# adaptador.net
KiCad netlist of a schematic drawn in Altium Designer
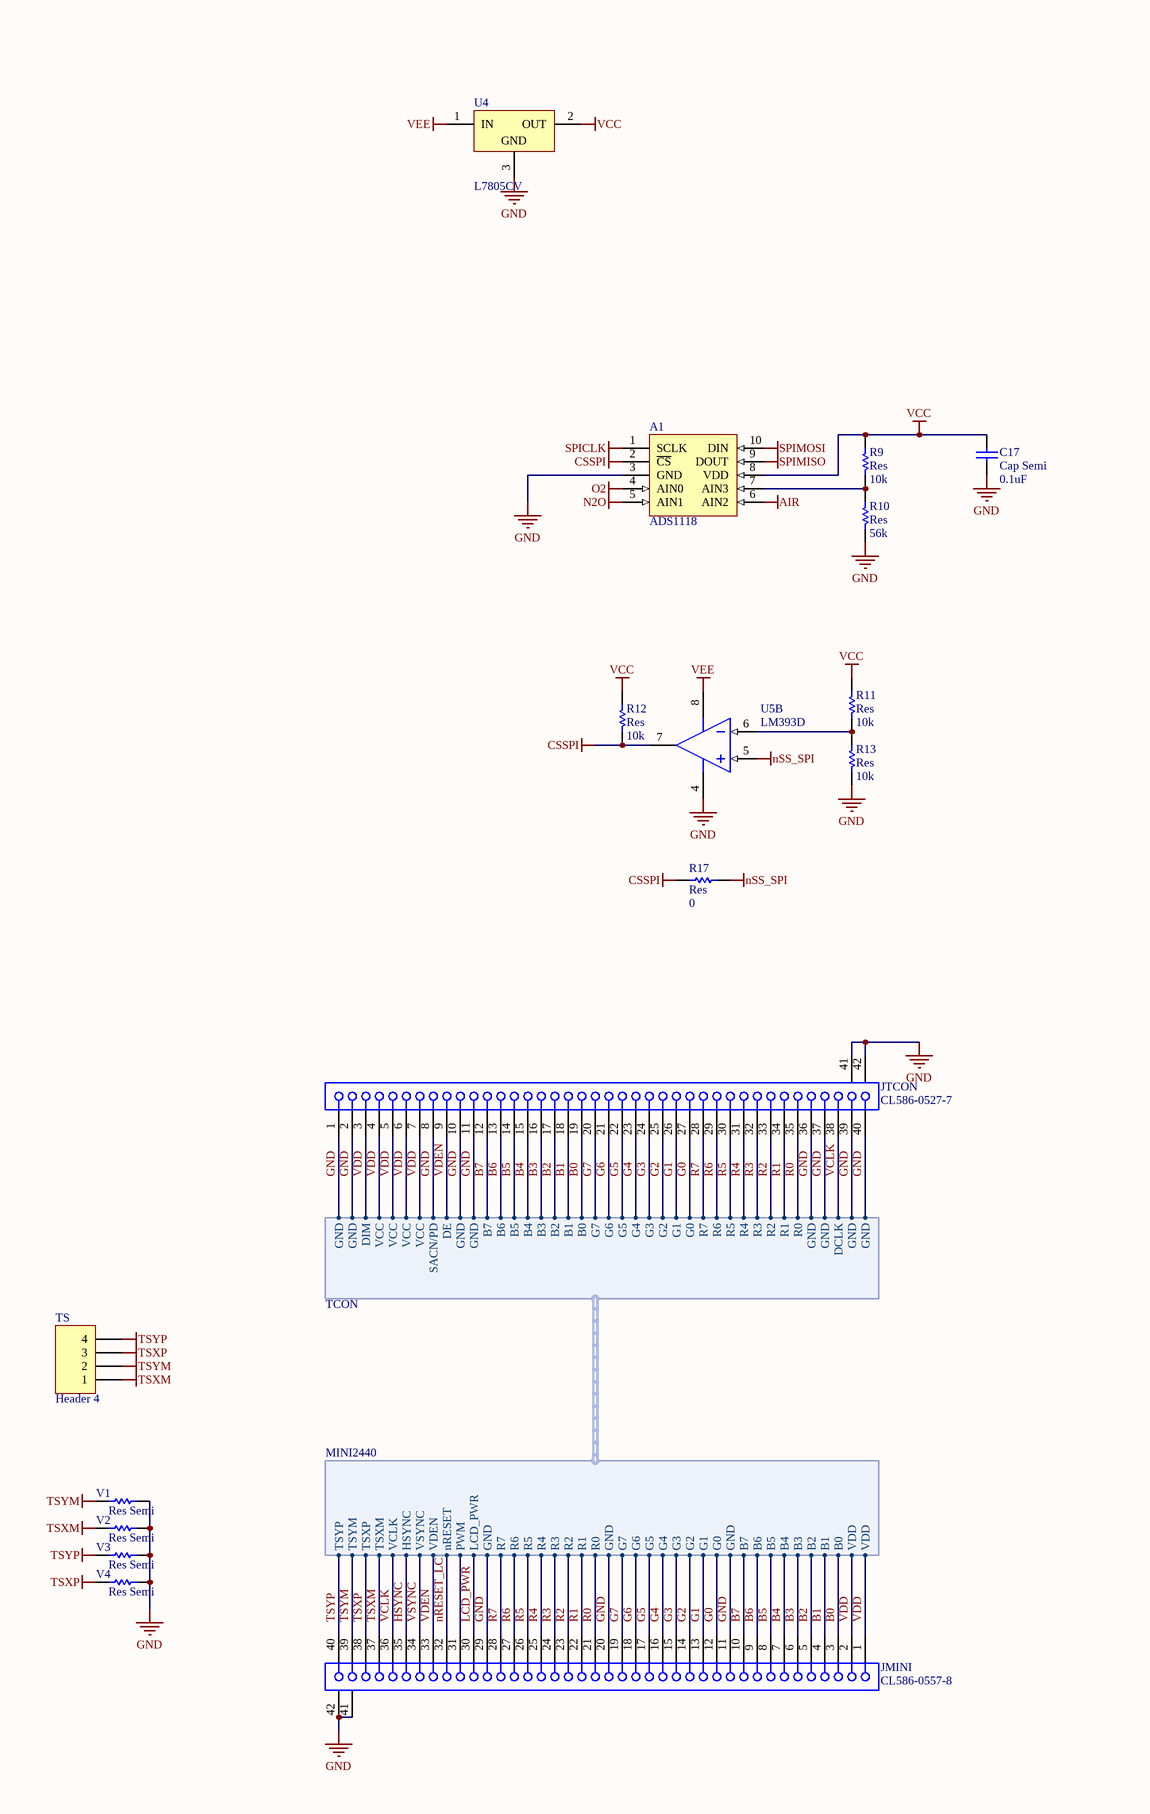
[diagram p0: adaptador.SchDoc, left]
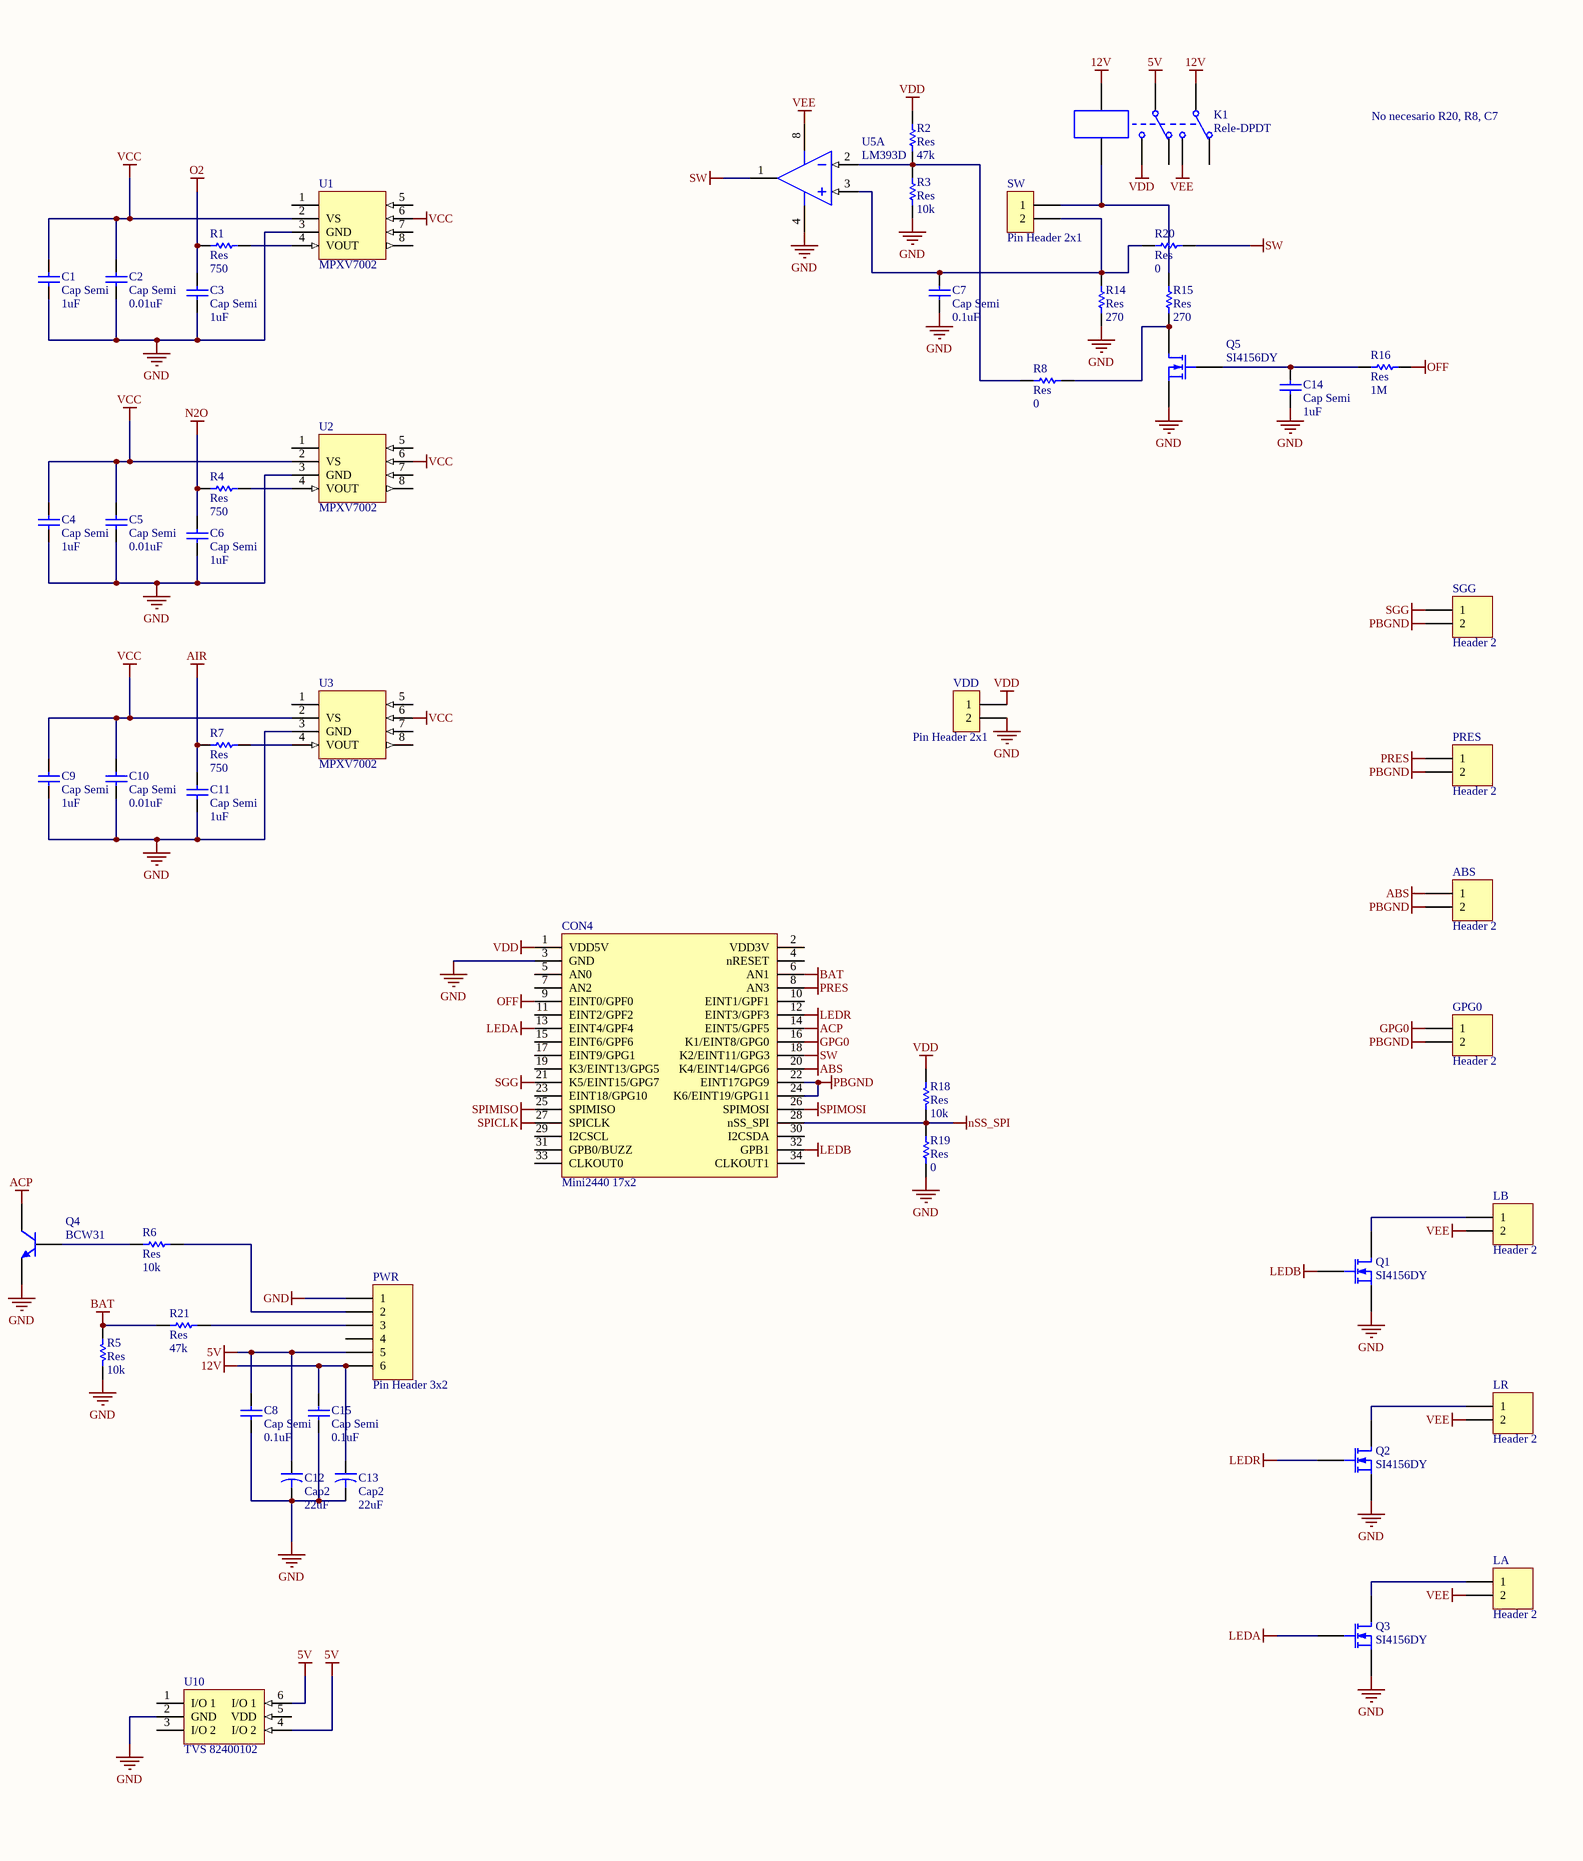
[diagram p1: adaptador.SchDoc, right]

(export (version "E")
  (design (tool "Eeschema 10.0.6"))
  (components
    (comp (ref "A1") (value "ADS1118") (footprint "MSOP-10") (libsource (lib "libreria") (part "ADS1118")))
    (comp (ref "ABS")
      (value "Header 2")
      (footprint "Sherlock2H")
      (description "mini_header 2x1")
      (libsource (lib "Miscellaneous Connectors") (part "Header 2"))
    )
    (comp (ref "C1")
      (value "Cap Semi")
      (footprint "8-1206")
      (description "Capacitor cerámico")
      (fields (field (name "ALTIUM_VALUE") "1uF"))
      (libsource (lib "Miscellaneous Devices") (part "Cap Semi"))
    )
    (comp (ref "C2")
      (value "Cap Semi")
      (footprint "8-1206")
      (description "Capacitor cerámico")
      (fields (field (name "ALTIUM_VALUE") "0.01uF"))
      (libsource (lib "Miscellaneous Devices") (part "Cap Semi"))
    )
    (comp (ref "C3")
      (value "Cap Semi")
      (footprint "8-1206")
      (description "Capacitor cerámico")
      (fields (field (name "ALTIUM_VALUE") "1uF"))
      (libsource (lib "Miscellaneous Devices") (part "Cap Semi"))
    )
    (comp (ref "C4")
      (value "Cap Semi")
      (footprint "8-1206")
      (description "Capacitor cerámico")
      (fields (field (name "ALTIUM_VALUE") "1uF"))
      (libsource (lib "Miscellaneous Devices") (part "Cap Semi"))
    )
    (comp (ref "C5")
      (value "Cap Semi")
      (footprint "8-1206")
      (description "Capacitor cerámico")
      (fields (field (name "ALTIUM_VALUE") "0.01uF"))
      (libsource (lib "Miscellaneous Devices") (part "Cap Semi"))
    )
    (comp (ref "C6")
      (value "Cap Semi")
      (footprint "8-1206")
      (description "Capacitor cerámico")
      (fields (field (name "ALTIUM_VALUE") "1uF"))
      (libsource (lib "Miscellaneous Devices") (part "Cap Semi"))
    )
    (comp (ref "C7")
      (value "Cap Semi")
      (footprint "8-1206")
      (description "Capacitor cerámico")
      (fields (field (name "ALTIUM_VALUE") "0.1uF"))
      (libsource (lib "Miscellaneous Devices") (part "Cap Semi"))
    )
    (comp (ref "C8")
      (value "Cap Semi")
      (footprint "8-1206")
      (description "Capacitor cerámico")
      (fields (field (name "ALTIUM_VALUE") "0.1uF"))
      (libsource (lib "Miscellaneous Devices") (part "Cap Semi"))
    )
    (comp (ref "C9")
      (value "Cap Semi")
      (footprint "8-1206")
      (description "Capacitor cerámico")
      (fields (field (name "ALTIUM_VALUE") "1uF"))
      (libsource (lib "Miscellaneous Devices") (part "Cap Semi"))
    )
    (comp (ref "C10")
      (value "Cap Semi")
      (footprint "8-1206")
      (description "Capacitor cerámico")
      (fields (field (name "ALTIUM_VALUE") "0.01uF"))
      (libsource (lib "Miscellaneous Devices") (part "Cap Semi"))
    )
    (comp (ref "C11")
      (value "Cap Semi")
      (footprint "8-1206")
      (description "Capacitor cerámico")
      (fields (field (name "ALTIUM_VALUE") "1uF"))
      (libsource (lib "Miscellaneous Devices") (part "Cap Semi"))
    )
    (comp (ref "C12")
      (value "Cap2")
      (footprint "CAPPR2-5x6.8")
      (description "Capacitor")
      (fields (field (name "ALTIUM_VALUE") "22uF") (field (name "PUBLISHER") "Altium Limited"))
      (libsource (lib "Miscellaneous Devices") (part "Cap2"))
    )
    (comp (ref "C13")
      (value "Cap2")
      (footprint "CAPPR2-5x6.8")
      (description "Capacitor")
      (fields (field (name "ALTIUM_VALUE") "22uF") (field (name "PUBLISHER") "Altium Limited"))
      (libsource (lib "Miscellaneous Devices") (part "Cap2"))
    )
    (comp (ref "C14")
      (value "Cap Semi")
      (footprint "8-1206")
      (description "Capacitor cerámico")
      (fields (field (name "ALTIUM_VALUE") "1uF"))
      (libsource (lib "Miscellaneous Devices") (part "Cap Semi"))
    )
    (comp (ref "C15")
      (value "Cap Semi")
      (footprint "8-1206")
      (description "Capacitor cerámico")
      (fields (field (name "ALTIUM_VALUE") "0.1uF"))
      (libsource (lib "Miscellaneous Devices") (part "Cap Semi"))
    )
    (comp (ref "C17")
      (value "Cap Semi")
      (footprint "8-1206")
      (description "Capacitor cerámico")
      (fields (field (name "ALTIUM_VALUE") "0.1uF"))
      (libsource (lib "Miscellaneous Devices") (part "Cap Semi"))
    )
    (comp (ref "CON4")
      (value "Mini2440 17x2")
      (footprint "HDR2X17HV")
      (description "Header, 17-Pin, Dual row")
      (fields (field (name "PUBLISHER") "Altium Limited"))
      (libsource (lib "libreria") (part "Mini2440 17x2"))
    )
    (comp (ref "GPG0")
      (value "Header 2")
      (footprint "Sherlock2H")
      (description "mini_header 2x1")
      (libsource (lib "Miscellaneous Connectors") (part "Header 2"))
    )
    (comp (ref "JMINI")
      (value "CL586-0557-8")
      (footprint "FH12-40S-0.5SHD")
      (description "FPC 40pos 0.5mm")
      (fields (field (name "MANUFACTURER") "OMRON") (field (name "PARTNUMBER") "XF2M-4015-1A"))
      (libsource (lib "HRS FPC-FFC FH12 Series") (part "CL586-0557-8"))
    )
    (comp (ref "JTCON")
      (value "CL586-0527-7")
      (footprint "FH12-40S-0.5SHD")
      (description "FPC 40pos 0.5mm")
      (fields (field (name "MANUFACTURER") "OMRON") (field (name "PARTNUMBER") "XF2M-4015-1A"))
      (libsource (lib "HRS FPC-FFC FH12 Series") (part "CL586-0527-7"))
    )
    (comp (ref "K1")
      (value "Rele-DPDT")
      (footprint "RELE-DPDT")
      (description "Dual-Pole Dual-Throw Relay")
      (fields (field (name "PUBLISHER") "Altium Limited"))
      (libsource (lib "libreria") (part "Rele-DPDT"))
    )
    (comp (ref "LA")
      (value "Header 2")
      (footprint "Sherlock2H")
      (description "mini_header 2x1")
      (fields (field (name "MANUFACTURER") "JST") (field (name "PARTNUMBER") "S2B-PH-K-S"))
      (libsource (lib "Miscellaneous Connectors") (part "Header 2"))
    )
    (comp (ref "LB")
      (value "Header 2")
      (footprint "Sherlock2H")
      (description "mini_header 2x1")
      (fields (field (name "MANUFACTURER") "JST") (field (name "PARTNUMBER") "S2B-PH-K-S"))
      (libsource (lib "Miscellaneous Connectors") (part "Header 2"))
    )
    (comp (ref "LR")
      (value "Header 2")
      (footprint "Sherlock2H")
      (description "mini_header 2x1")
      (fields (field (name "MANUFACTURER") "JST") (field (name "PARTNUMBER") "S2B-PH-K-S"))
      (libsource (lib "Miscellaneous Connectors") (part "Header 2"))
    )
    (comp (ref "PRES")
      (value "Header 2")
      (footprint "Sherlock2H")
      (description "mini_header 2x1")
      (fields (field (name "MANUFACTURER") "JST") (field (name "PARTNUMBER") "S2B-PH-K-S"))
      (libsource (lib "Miscellaneous Connectors") (part "Header 2"))
    )
    (comp (ref "PWR")
      (value "Pin Header 3x2")
      (footprint "bigHDR2X3")
      (description "Minifit 6pos v/h 4.2mm")
      (fields (field (name "MANUFACTURER") "JST") (field (name "PARTNUMBER") "S2B-PH-K-S"))
      (libsource (lib "libreria") (part "Vertical Pin Header 3x2"))
    )
    (comp (ref "Q1")
      (value "SI4156DY")
      (footprint "SO8_M_MOSFET")
      (description "N-Channel MOSFET")
      (fields (field (name "MANUFACTURER") "Vishay"))
      (libsource (lib "Miscellaneous Devices") (part "MOSFET-N"))
    )
    (comp (ref "Q2")
      (value "SI4156DY")
      (footprint "SO8_M_MOSFET")
      (description "N-Channel MOSFET")
      (fields (field (name "MANUFACTURER") "Vishay"))
      (libsource (lib "Miscellaneous Devices") (part "MOSFET-N"))
    )
    (comp (ref "Q3")
      (value "SI4156DY")
      (footprint "SO8_M_MOSFET")
      (description "N-Channel MOSFET")
      (fields (field (name "MANUFACTURER") "Vishay"))
      (libsource (lib "Miscellaneous Devices") (part "MOSFET-N"))
    )
    (comp (ref "Q4")
      (value "BCW31")
      (footprint "SOT-23A")
      (description "NPN Epitaxial Silicon Transistor")
      (fields (field (name "PUBLISHER") "Altium Limited"))
      (libsource (lib "FSC Discrete BJT") (part "BCW31"))
    )
    (comp (ref "Q5")
      (value "SI4156DY")
      (footprint "SO8_M_MOSFET")
      (description "N-Channel MOSFET")
      (fields (field (name "MANUFACTURER") "Vishay"))
      (libsource (lib "Miscellaneous Devices") (part "MOSFET-N"))
    )
    (comp (ref "R1")
      (value "Res")
      (footprint "8-1206")
      (description "Resistor")
      (fields (field (name "ALTIUM_VALUE") "750"))
      (libsource (lib "libreria") (part "Res"))
    )
    (comp (ref "R2")
      (value "Res")
      (footprint "8-1206")
      (description "Resistor")
      (fields (field (name "ALTIUM_VALUE") "47k"))
      (libsource (lib "libreria") (part "Res"))
    )
    (comp (ref "R3")
      (value "Res")
      (footprint "8-1206")
      (description "Resistor")
      (fields (field (name "ALTIUM_VALUE") "10k"))
      (libsource (lib "libreria") (part "Res"))
    )
    (comp (ref "R4")
      (value "Res")
      (footprint "8-1206")
      (description "Resistor")
      (fields (field (name "ALTIUM_VALUE") "750"))
      (libsource (lib "libreria") (part "Res"))
    )
    (comp (ref "R5")
      (value "Res")
      (footprint "8-1206")
      (description "Resistor")
      (fields (field (name "ALTIUM_VALUE") "10k"))
      (libsource (lib "libreria") (part "Res"))
    )
    (comp (ref "R6")
      (value "Res")
      (footprint "8-1206")
      (description "Resistor")
      (fields (field (name "ALTIUM_VALUE") "10k"))
      (libsource (lib "libreria") (part "Res"))
    )
    (comp (ref "R7")
      (value "Res")
      (footprint "8-1206")
      (description "Resistor")
      (fields (field (name "ALTIUM_VALUE") "750"))
      (libsource (lib "libreria") (part "Res"))
    )
    (comp (ref "R8")
      (value "Res")
      (footprint "8-1206")
      (description "Resistor")
      (fields (field (name "ALTIUM_VALUE") "0"))
      (libsource (lib "libreria") (part "Res"))
    )
    (comp (ref "R9")
      (value "Res")
      (footprint "8-1206")
      (description "Resistor")
      (fields (field (name "ALTIUM_VALUE") "10k"))
      (libsource (lib "libreria") (part "Res"))
    )
    (comp (ref "R10")
      (value "Res")
      (footprint "8-1206")
      (description "Resistor")
      (fields (field (name "ALTIUM_VALUE") "56k"))
      (libsource (lib "libreria") (part "Res"))
    )
    (comp (ref "R11")
      (value "Res")
      (footprint "8-1206")
      (description "Resistor")
      (fields (field (name "ALTIUM_VALUE") "10k"))
      (libsource (lib "libreria") (part "Res"))
    )
    (comp (ref "R12")
      (value "Res")
      (footprint "8-1206")
      (description "Resistor")
      (fields (field (name "ALTIUM_VALUE") "10k"))
      (libsource (lib "libreria") (part "Res"))
    )
    (comp (ref "R13")
      (value "Res")
      (footprint "8-1206")
      (description "Resistor")
      (fields (field (name "ALTIUM_VALUE") "10k"))
      (libsource (lib "libreria") (part "Res"))
    )
    (comp (ref "R14")
      (value "Res")
      (footprint "8-1206")
      (description "Resistor")
      (fields (field (name "ALTIUM_VALUE") "270"))
      (libsource (lib "libreria") (part "Res"))
    )
    (comp (ref "R15")
      (value "Res")
      (footprint "8-1206")
      (description "Resistor")
      (fields (field (name "ALTIUM_VALUE") "270"))
      (libsource (lib "libreria") (part "Res"))
    )
    (comp (ref "R16")
      (value "Res")
      (footprint "8-1206")
      (description "Resistor")
      (fields (field (name "ALTIUM_VALUE") "1M"))
      (libsource (lib "libreria") (part "Res"))
    )
    (comp (ref "R17")
      (value "Res")
      (footprint "8-1206")
      (description "Resistor")
      (fields (field (name "ALTIUM_VALUE") "0"))
      (libsource (lib "libreria") (part "Res"))
    )
    (comp (ref "R18")
      (value "Res")
      (footprint "8-1206")
      (description "Resistor")
      (fields (field (name "ALTIUM_VALUE") "10k"))
      (libsource (lib "libreria") (part "Res"))
    )
    (comp (ref "R19")
      (value "Res")
      (footprint "8-1206")
      (description "Resistor")
      (fields (field (name "ALTIUM_VALUE") "0"))
      (libsource (lib "libreria") (part "Res"))
    )
    (comp (ref "R20")
      (value "Res")
      (footprint "8-1206")
      (description "Resistor")
      (fields (field (name "ALTIUM_VALUE") "0"))
      (libsource (lib "libreria") (part "Res"))
    )
    (comp (ref "R21")
      (value "Res")
      (footprint "8-1206")
      (description "Resistor")
      (fields (field (name "ALTIUM_VALUE") "47k"))
      (libsource (lib "libreria") (part "Res"))
    )
    (comp (ref "SGG")
      (value "Header 2")
      (footprint "Sherlock2H")
      (description "mini_header 2x1")
      (fields (field (name "MANUFACTURER") "JST") (field (name "PARTNUMBER") "S2B-PH-K-S"))
      (libsource (lib "Miscellaneous Connectors") (part "Header 2"))
    )
    (comp (ref "SW")
      (value "Pin Header 2x1")
      (footprint "Sherlock2H")
      (description "mini_header 2x1")
      (fields (field (name "MANUFACTURER") "JST") (field (name "PARTNUMBER") "S2B-PH-K-S"))
      (libsource (lib "libreria") (part "Vertical Pin Header PCB 2x1"))
    )
    (comp (ref "TS")
      (value "Header 4")
      (footprint "HDR1X4")
      (description "Header 4pos 2.54mm")
      (libsource (lib "Miscellaneous Connectors") (part "Header 4"))
    )
    (comp (ref "U1")
      (value "MPXV7002")
      (footprint "CASE 1351-01")
      (description "Sensor de presión diferencial")
      (libsource (lib "libreria") (part "MPXV7002"))
    )
    (comp (ref "U2")
      (value "MPXV7002")
      (footprint "CASE 1351-01")
      (description "Sensor de presión diferencial")
      (libsource (lib "libreria") (part "MPXV7002"))
    )
    (comp (ref "U3")
      (value "MPXV7002")
      (footprint "CASE 1351-01")
      (description "Sensor de presión diferencial")
      (libsource (lib "libreria") (part "MPXV7002"))
    )
    (comp (ref "U4")
      (value "L7805CV")
      (footprint "TO220ABN")
      (description "Positive Voltage Regulator")
      (fields (field (name "PUBLISHER") "Altium Limited"))
      (libsource (lib "ST Power Mgt Voltage Regulator") (part "L7805CV"))
    )
    (comp (ref "U5")
      (value "LM393D")
      (footprint "SO8_M")
      (description "Low-Power Dual Voltage Comparator")
      (fields (field (name "PUBLISHER") "Altium Limited"))
      (libsource (lib "ST Analog Comparator") (part "LM393D"))
    )
    (comp (ref "U10")
      (value "TVS 82400102")
      (footprint "SOT23-6")
      (description "Electric Field Imaging Device")
      (libsource (lib "libreria") (part "TVS 82400102"))
    )
    (comp (ref "V1")
      (value "Res Semi")
      (footprint "RESC1608L")
      (description "Semiconductor Resistor")
      (fields (field (name "PUBLISHER") "Altium Limited"))
      (libsource (lib "Miscellaneous Devices") (part "Res Semi"))
    )
    (comp (ref "V2")
      (value "Res Semi")
      (footprint "RESC1608L")
      (description "Semiconductor Resistor")
      (fields (field (name "PUBLISHER") "Altium Limited"))
      (libsource (lib "Miscellaneous Devices") (part "Res Semi"))
    )
    (comp (ref "V3")
      (value "Res Semi")
      (footprint "RESC1608L")
      (description "Semiconductor Resistor")
      (fields (field (name "PUBLISHER") "Altium Limited"))
      (libsource (lib "Miscellaneous Devices") (part "Res Semi"))
    )
    (comp (ref "V4")
      (value "Res Semi")
      (footprint "RESC1608L")
      (description "Semiconductor Resistor")
      (fields (field (name "PUBLISHER") "Altium Limited"))
      (libsource (lib "Miscellaneous Devices") (part "Res Semi"))
    )
    (comp (ref "VDD")
      (value "Pin Header 2x1")
      (footprint "Sherlock2H")
      (description "mini_header 2x1")
      (fields (field (name "MANUFACTURER") "JST") (field (name "PARTNUMBER") "S2B-PH-K-S"))
      (libsource (lib "libreria") (part "Vertical Pin Header PCB 2x1"))
    )
  )
  (nets
    (net (code "2") (name "/B0") (class "Default")
      (node (ref "JMINI") (pin "3") (pinfunction "3_3") (pintype "passive"))
      (node (ref "JTCON") (pin "19") (pinfunction "19_19") (pintype "passive"))
    )
    (net (code "3") (name "/B1") (class "Default")
      (node (ref "JMINI") (pin "4") (pinfunction "4_4") (pintype "passive"))
      (node (ref "JTCON") (pin "18") (pinfunction "18_18") (pintype "passive"))
    )
    (net (code "4") (name "/B2") (class "Default")
      (node (ref "JMINI") (pin "5") (pinfunction "5_5") (pintype "passive"))
      (node (ref "JTCON") (pin "17") (pinfunction "17_17") (pintype "passive"))
    )
    (net (code "5") (name "/B3") (class "Default")
      (node (ref "JMINI") (pin "6") (pinfunction "6_6") (pintype "passive"))
      (node (ref "JTCON") (pin "16") (pinfunction "16_16") (pintype "passive"))
    )
    (net (code "6") (name "/B4") (class "Default")
      (node (ref "JMINI") (pin "7") (pinfunction "7_7") (pintype "passive"))
      (node (ref "JTCON") (pin "15") (pinfunction "15_15") (pintype "passive"))
    )
    (net (code "7") (name "/B5") (class "Default")
      (node (ref "JMINI") (pin "8") (pinfunction "8_8") (pintype "passive"))
      (node (ref "JTCON") (pin "14") (pinfunction "14_14") (pintype "passive"))
    )
    (net (code "8") (name "/B6") (class "Default")
      (node (ref "JMINI") (pin "9") (pinfunction "9_9") (pintype "passive"))
      (node (ref "JTCON") (pin "13") (pinfunction "13_13") (pintype "passive"))
    )
    (net (code "9") (name "/B7") (class "Default")
      (node (ref "JMINI") (pin "10") (pinfunction "10_10") (pintype "passive"))
      (node (ref "JTCON") (pin "12") (pinfunction "12_12") (pintype "passive"))
    )
    (net (code "10") (name "/G0") (class "Default")
      (node (ref "JMINI") (pin "12") (pinfunction "12_12") (pintype "passive"))
      (node (ref "JTCON") (pin "27") (pinfunction "27_27") (pintype "passive"))
    )
    (net (code "11") (name "/G1") (class "Default")
      (node (ref "JMINI") (pin "13") (pinfunction "13_13") (pintype "passive"))
      (node (ref "JTCON") (pin "26") (pinfunction "26_26") (pintype "passive"))
    )
    (net (code "12") (name "/G2") (class "Default")
      (node (ref "JMINI") (pin "14") (pinfunction "14_14") (pintype "passive"))
      (node (ref "JTCON") (pin "25") (pinfunction "25_25") (pintype "passive"))
    )
    (net (code "13") (name "/G3") (class "Default")
      (node (ref "JMINI") (pin "15") (pinfunction "15_15") (pintype "passive"))
      (node (ref "JTCON") (pin "24") (pinfunction "24_24") (pintype "passive"))
    )
    (net (code "14") (name "/G4") (class "Default")
      (node (ref "JMINI") (pin "16") (pinfunction "16_16") (pintype "passive"))
      (node (ref "JTCON") (pin "23") (pinfunction "23_23") (pintype "passive"))
    )
    (net (code "15") (name "/G5") (class "Default")
      (node (ref "JMINI") (pin "17") (pinfunction "17_17") (pintype "passive"))
      (node (ref "JTCON") (pin "22") (pinfunction "22_22") (pintype "passive"))
    )
    (net (code "16") (name "/G6") (class "Default")
      (node (ref "JMINI") (pin "18") (pinfunction "18_18") (pintype "passive"))
      (node (ref "JTCON") (pin "21") (pinfunction "21_21") (pintype "passive"))
    )
    (net (code "17") (name "/G7") (class "Default")
      (node (ref "JMINI") (pin "19") (pinfunction "19_19") (pintype "passive"))
      (node (ref "JTCON") (pin "20") (pinfunction "20_20") (pintype "passive"))
    )
    (net (code "18") (name "/HSYNC") (class "Default")
      (node (ref "JMINI") (pin "35") (pinfunction "35_35") (pintype "passive"))
    )
    (net (code "19") (name "/LCD_PWR") (class "Default")
      (node (ref "JMINI") (pin "30") (pinfunction "30_30") (pintype "passive"))
    )
    (net (code "20") (name "/PWM") (class "Default")
      (node (ref "JMINI") (pin "31") (pinfunction "31_31") (pintype "passive"))
    )
    (net (code "21") (name "/R0") (class "Default")
      (node (ref "JMINI") (pin "21") (pinfunction "21_21") (pintype "passive"))
      (node (ref "JTCON") (pin "35") (pinfunction "35_35") (pintype "passive"))
    )
    (net (code "22") (name "/R1") (class "Default")
      (node (ref "JMINI") (pin "22") (pinfunction "22_22") (pintype "passive"))
      (node (ref "JTCON") (pin "34") (pinfunction "34_34") (pintype "passive"))
    )
    (net (code "23") (name "/R2") (class "Default")
      (node (ref "JMINI") (pin "23") (pinfunction "23_23") (pintype "passive"))
      (node (ref "JTCON") (pin "33") (pinfunction "33_33") (pintype "passive"))
    )
    (net (code "24") (name "/R3") (class "Default")
      (node (ref "JMINI") (pin "24") (pinfunction "24_24") (pintype "passive"))
      (node (ref "JTCON") (pin "32") (pinfunction "32_32") (pintype "passive"))
    )
    (net (code "25") (name "/R4") (class "Default")
      (node (ref "JMINI") (pin "25") (pinfunction "25_25") (pintype "passive"))
      (node (ref "JTCON") (pin "31") (pinfunction "31_31") (pintype "passive"))
    )
    (net (code "26") (name "/R5") (class "Default")
      (node (ref "JMINI") (pin "26") (pinfunction "26_26") (pintype "passive"))
      (node (ref "JTCON") (pin "30") (pinfunction "30_30") (pintype "passive"))
    )
    (net (code "27") (name "/R6") (class "Default")
      (node (ref "JMINI") (pin "27") (pinfunction "27_27") (pintype "passive"))
      (node (ref "JTCON") (pin "29") (pinfunction "29_29") (pintype "passive"))
    )
    (net (code "28") (name "/R7") (class "Default")
      (node (ref "JMINI") (pin "28") (pinfunction "28_28") (pintype "passive"))
      (node (ref "JTCON") (pin "28") (pinfunction "28_28") (pintype "passive"))
    )
    (net (code "29") (name "/VCLK") (class "Default")
      (node (ref "JMINI") (pin "36") (pinfunction "36_36") (pintype "passive"))
      (node (ref "JTCON") (pin "38") (pinfunction "38_38") (pintype "passive"))
    )
    (net (code "30") (name "/VDEN") (class "Default")
      (node (ref "JMINI") (pin "33") (pinfunction "33_33") (pintype "passive"))
      (node (ref "JTCON") (pin "9") (pinfunction "9_9") (pintype "passive"))
    )
    (net (code "31") (name "/VSYNC") (class "Default")
      (node (ref "JMINI") (pin "34") (pinfunction "34_34") (pintype "passive"))
    )
    (net (code "32") (name "/nRESET_LCD") (class "Default")
      (node (ref "JMINI") (pin "32") (pinfunction "32_32") (pintype "passive"))
    )
    (net (code "34") (name "5V") (class "Default")
      (node (ref "C12") (pin "1") (pinfunction "1_1") (pintype "passive"))
      (node (ref "C8") (pin "2") (pinfunction "2_2") (pintype "passive"))
      (node (ref "K1") (pin "7") (pinfunction "7_7") (pintype "passive"))
      (node (ref "PWR") (pin "5") (pinfunction "5_5") (pintype "passive"))
      (node (ref "U10") (pin "4") (pinfunction "I/O_2_4") (pintype "input"))
      (node (ref "U10") (pin "6") (pinfunction "I/O_1_6") (pintype "input"))
    )
    (net (code "35") (name "12V") (class "Default")
      (node (ref "C13") (pin "1") (pinfunction "1_1") (pintype "passive"))
      (node (ref "C15") (pin "2") (pinfunction "2_2") (pintype "passive"))
      (node (ref "K1") (pin "2") (pinfunction "2_2") (pintype "passive"))
      (node (ref "K1") (pin "8") (pinfunction "8_8") (pintype "passive"))
      (node (ref "PWR") (pin "6") (pinfunction "6_6") (pintype "passive"))
    )
    (net (code "36") (name "ABS") (class "Default")
      (node (ref "ABS") (pin "1") (pinfunction "1_1") (pintype "passive"))
      (node (ref "CON4") (pin "20") (pinfunction "K4/EINT14/GPG6_20") (pintype "passive"))
    )
    (net (code "37") (name "ACP") (class "Default")
      (node (ref "CON4") (pin "14") (pinfunction "EINT5/GPF5_14") (pintype "passive"))
      (node (ref "Q4") (pin "3") (pinfunction "C_3") (pintype "passive"))
    )
    (net (code "38") (name "AIR") (class "Default")
      (node (ref "A1") (pin "6") (pinfunction "AIN2_6") (pintype "input"))
      (node (ref "C11") (pin "2") (pinfunction "2_2") (pintype "passive"))
      (node (ref "R7") (pin "1") (pinfunction "1_1") (pintype "passive"))
    )
    (net (code "39") (name "BAT") (class "Default")
      (node (ref "CON4") (pin "6") (pinfunction "AN1_6") (pintype "passive"))
      (node (ref "R21") (pin "2") (pinfunction "2_2") (pintype "passive"))
      (node (ref "R5") (pin "1") (pinfunction "1_1") (pintype "passive"))
    )
    (net (code "40") (name "CSSPI") (class "Default")
      (node (ref "A1") (pin "2") (pinfunction "~{CS}_2") (pintype "power_in"))
      (node (ref "R12") (pin "2") (pinfunction "2_2") (pintype "passive"))
      (node (ref "R17") (pin "2") (pinfunction "2_2") (pintype "passive"))
      (node (ref "U5") (pin "7") (pinfunction "OUT_7") (pintype "open_collector"))
    )
    (net (code "41") (name "GND") (class "Default")
      (node (ref "A1") (pin "3") (pinfunction "GND_3") (pintype "power_in"))
      (node (ref "C1") (pin "1") (pinfunction "1_1") (pintype "passive"))
      (node (ref "C10") (pin "1") (pinfunction "1_1") (pintype "passive"))
      (node (ref "C11") (pin "1") (pinfunction "1_1") (pintype "passive"))
      (node (ref "C12") (pin "2") (pinfunction "2_2") (pintype "passive"))
      (node (ref "C13") (pin "2") (pinfunction "2_2") (pintype "passive"))
      (node (ref "C14") (pin "1") (pinfunction "1_1") (pintype "passive"))
      (node (ref "C15") (pin "1") (pinfunction "1_1") (pintype "passive"))
      (node (ref "C17") (pin "1") (pinfunction "1_1") (pintype "passive"))
      (node (ref "C2") (pin "1") (pinfunction "1_1") (pintype "passive"))
      (node (ref "C3") (pin "1") (pinfunction "1_1") (pintype "passive"))
      (node (ref "C4") (pin "1") (pinfunction "1_1") (pintype "passive"))
      (node (ref "C5") (pin "1") (pinfunction "1_1") (pintype "passive"))
      (node (ref "C6") (pin "1") (pinfunction "1_1") (pintype "passive"))
      (node (ref "C7") (pin "1") (pinfunction "1_1") (pintype "passive"))
      (node (ref "C8") (pin "1") (pinfunction "1_1") (pintype "passive"))
      (node (ref "C9") (pin "1") (pinfunction "1_1") (pintype "passive"))
      (node (ref "CON4") (pin "3") (pinfunction "GND_3") (pintype "passive"))
      (node (ref "JMINI") (pin "11") (pinfunction "11_11") (pintype "passive"))
      (node (ref "JMINI") (pin "20") (pinfunction "20_20") (pintype "passive"))
      (node (ref "JMINI") (pin "29") (pinfunction "29_29") (pintype "passive"))
      (node (ref "JMINI") (pin "41") (pinfunction "MH1_41") (pintype "passive"))
      (node (ref "JMINI") (pin "42") (pinfunction "MH2_42") (pintype "passive"))
      (node (ref "JTCON") (pin "1") (pinfunction "1_1") (pintype "passive"))
      (node (ref "JTCON") (pin "10") (pinfunction "10_10") (pintype "passive"))
      (node (ref "JTCON") (pin "11") (pinfunction "11_11") (pintype "passive"))
      (node (ref "JTCON") (pin "2") (pinfunction "2_2") (pintype "passive"))
      (node (ref "JTCON") (pin "36") (pinfunction "36_36") (pintype "passive"))
      (node (ref "JTCON") (pin "37") (pinfunction "37_37") (pintype "passive"))
      (node (ref "JTCON") (pin "39") (pinfunction "39_39") (pintype "passive"))
      (node (ref "JTCON") (pin "40") (pinfunction "40_40") (pintype "passive"))
      (node (ref "JTCON") (pin "41") (pinfunction "MH1_41") (pintype "passive"))
      (node (ref "JTCON") (pin "42") (pinfunction "MH2_42") (pintype "passive"))
      (node (ref "JTCON") (pin "8") (pinfunction "8_8") (pintype "passive"))
      (node (ref "PWR") (pin "1") (pinfunction "1_1") (pintype "passive"))
      (node (ref "Q1") (pin "3") (pinfunction "S_3") (pintype "passive"))
      (node (ref "Q2") (pin "3") (pinfunction "S_3") (pintype "passive"))
      (node (ref "Q3") (pin "3") (pinfunction "S_3") (pintype "passive"))
      (node (ref "Q4") (pin "2") (pinfunction "E_2") (pintype "passive"))
      (node (ref "Q5") (pin "3") (pinfunction "S_3") (pintype "passive"))
      (node (ref "R10") (pin "1") (pinfunction "1_1") (pintype "passive"))
      (node (ref "R13") (pin "2") (pinfunction "2_2") (pintype "passive"))
      (node (ref "R14") (pin "1") (pinfunction "1_1") (pintype "passive"))
      (node (ref "R19") (pin "2") (pinfunction "2_2") (pintype "passive"))
      (node (ref "R3") (pin "1") (pinfunction "1_1") (pintype "passive"))
      (node (ref "R5") (pin "2") (pinfunction "2_2") (pintype "passive"))
      (node (ref "U1") (pin "3") (pinfunction "GND_3") (pintype "power_in"))
      (node (ref "U10") (pin "2") (pinfunction "GND_2") (pintype "power_in"))
      (node (ref "U2") (pin "3") (pinfunction "GND_3") (pintype "power_in"))
      (node (ref "U3") (pin "3") (pinfunction "GND_3") (pintype "power_in"))
      (node (ref "U4") (pin "3") (pinfunction "GND_3") (pintype "power_in"))
      (node (ref "U5") (pin "4") (pinfunction "V-_4") (pintype "power_in"))
      (node (ref "V1") (pin "2") (pinfunction "2_2") (pintype "passive"))
      (node (ref "V2") (pin "2") (pinfunction "2_2") (pintype "passive"))
      (node (ref "V3") (pin "2") (pinfunction "2_2") (pintype "passive"))
      (node (ref "V4") (pin "2") (pinfunction "2_2") (pintype "passive"))
      (node (ref "VDD") (pin "2") (pinfunction "2_2") (pintype "passive"))
    )
    (net (code "42") (name "GPG0") (class "Default")
      (node (ref "CON4") (pin "16") (pinfunction "K1/EINT8/GPG0_16") (pintype "passive"))
      (node (ref "GPG0") (pin "1") (pinfunction "1_1") (pintype "passive"))
    )
    (net (code "43") (name "LEDA") (class "Default")
      (node (ref "CON4") (pin "13") (pinfunction "EINT4/GPF4_13") (pintype "passive"))
      (node (ref "Q3") (pin "2") (pinfunction "G_2") (pintype "passive"))
    )
    (net (code "44") (name "LEDB") (class "Default")
      (node (ref "CON4") (pin "32") (pinfunction "GPB1_32") (pintype "passive"))
      (node (ref "Q1") (pin "2") (pinfunction "G_2") (pintype "passive"))
    )
    (net (code "45") (name "LEDR") (class "Default")
      (node (ref "CON4") (pin "12") (pinfunction "EINT3/GPF3_12") (pintype "passive"))
      (node (ref "Q2") (pin "2") (pinfunction "G_2") (pintype "passive"))
    )
    (net (code "46") (name "N2O") (class "Default")
      (node (ref "A1") (pin "5") (pinfunction "AIN1_5") (pintype "input"))
      (node (ref "C6") (pin "2") (pinfunction "2_2") (pintype "passive"))
      (node (ref "R4") (pin "1") (pinfunction "1_1") (pintype "passive"))
    )
    (net (code "47") (name "Net-(A1-AIN3)") (class "Default")
      (node (ref "A1") (pin "7") (pinfunction "AIN3_7") (pintype "input"))
      (node (ref "R10") (pin "2") (pinfunction "2_2") (pintype "passive"))
      (node (ref "R9") (pin "1") (pinfunction "1_1") (pintype "passive"))
    )
    (net (code "48") (name "Net-(K1-Pad1)") (class "Default")
      (node (ref "K1") (pin "1") (pinfunction "1_1") (pintype "passive"))
      (node (ref "R15") (pin "2") (pinfunction "2_2") (pintype "passive"))
      (node (ref "SW") (pin "1") (pinfunction "1_1") (pintype "passive"))
    )
    (net (code "49") (name "Net-(PWR-Pad2)") (class "Default")
      (node (ref "PWR") (pin "2") (pinfunction "2_2") (pintype "passive"))
      (node (ref "R6") (pin "2") (pinfunction "2_2") (pintype "passive"))
    )
    (net (code "50") (name "Net-(PWR-Pad3)") (class "Default")
      (node (ref "PWR") (pin "3") (pinfunction "3_3") (pintype "passive"))
      (node (ref "R21") (pin "1") (pinfunction "1_1") (pintype "passive"))
    )
    (net (code "51") (name "Net-(Q1-D)") (class "Default")
      (node (ref "LB") (pin "1") (pinfunction "1_1") (pintype "passive"))
      (node (ref "Q1") (pin "1") (pinfunction "D_1") (pintype "passive"))
    )
    (net (code "52") (name "Net-(Q2-D)") (class "Default")
      (node (ref "LR") (pin "1") (pinfunction "1_1") (pintype "passive"))
      (node (ref "Q2") (pin "1") (pinfunction "D_1") (pintype "passive"))
    )
    (net (code "53") (name "Net-(Q3-D)") (class "Default")
      (node (ref "LA") (pin "1") (pinfunction "1_1") (pintype "passive"))
      (node (ref "Q3") (pin "1") (pinfunction "D_1") (pintype "passive"))
    )
    (net (code "54") (name "Net-(Q4-B)") (class "Default")
      (node (ref "Q4") (pin "1") (pinfunction "B_1") (pintype "passive"))
      (node (ref "R6") (pin "1") (pinfunction "1_1") (pintype "passive"))
    )
    (net (code "55") (name "Net-(Q5-D)") (class "Default")
      (node (ref "Q5") (pin "1") (pinfunction "D_1") (pintype "passive"))
      (node (ref "R15") (pin "1") (pinfunction "1_1") (pintype "passive"))
      (node (ref "R8") (pin "1") (pinfunction "1_1") (pintype "passive"))
    )
    (net (code "56") (name "Net-(Q5-G)") (class "Default")
      (node (ref "C14") (pin "2") (pinfunction "2_2") (pintype "passive"))
      (node (ref "Q5") (pin "2") (pinfunction "G_2") (pintype "passive"))
      (node (ref "R16") (pin "2") (pinfunction "2_2") (pintype "passive"))
    )
    (net (code "57") (name "Net-(U1-VOUT)") (class "Default")
      (node (ref "R1") (pin "2") (pinfunction "2_2") (pintype "passive"))
      (node (ref "U1") (pin "4") (pinfunction "VOUT_4") (pintype "input"))
    )
    (net (code "58") (name "Net-(U2-VOUT)") (class "Default")
      (node (ref "R4") (pin "2") (pinfunction "2_2") (pintype "passive"))
      (node (ref "U2") (pin "4") (pinfunction "VOUT_4") (pintype "input"))
    )
    (net (code "59") (name "Net-(U3-VOUT)") (class "Default")
      (node (ref "R7") (pin "2") (pinfunction "2_2") (pintype "passive"))
      (node (ref "U3") (pin "4") (pinfunction "VOUT_4") (pintype "input"))
    )
    (net (code "60") (name "Net-(U5A-IN+)") (class "Default")
      (node (ref "C7") (pin "2") (pinfunction "2_2") (pintype "passive"))
      (node (ref "R14") (pin "2") (pinfunction "2_2") (pintype "passive"))
      (node (ref "R20") (pin "2") (pinfunction "2_2") (pintype "passive"))
      (node (ref "SW") (pin "2") (pinfunction "2_2") (pintype "passive"))
      (node (ref "U5") (pin "3") (pinfunction "IN+_3") (pintype "input"))
    )
    (net (code "61") (name "Net-(U5A-IN-)") (class "Default")
      (node (ref "R2") (pin "1") (pinfunction "1_1") (pintype "passive"))
      (node (ref "R3") (pin "2") (pinfunction "2_2") (pintype "passive"))
      (node (ref "R8") (pin "2") (pinfunction "2_2") (pintype "passive"))
      (node (ref "U5") (pin "2") (pinfunction "IN-_2") (pintype "input"))
    )
    (net (code "62") (name "Net-(U5B-IN-)") (class "Default")
      (node (ref "R11") (pin "2") (pinfunction "2_2") (pintype "passive"))
      (node (ref "R13") (pin "1") (pinfunction "1_1") (pintype "passive"))
      (node (ref "U5") (pin "6") (pinfunction "IN-_6") (pintype "input"))
    )
    (net (code "63") (name "O2") (class "Default")
      (node (ref "A1") (pin "4") (pinfunction "AIN0_4") (pintype "input"))
      (node (ref "C3") (pin "2") (pinfunction "2_2") (pintype "passive"))
      (node (ref "R1") (pin "1") (pinfunction "1_1") (pintype "passive"))
    )
    (net (code "64") (name "OFF") (class "Default")
      (node (ref "CON4") (pin "9") (pinfunction "EINT0/GPF0_9") (pintype "passive"))
      (node (ref "R16") (pin "1") (pinfunction "1_1") (pintype "passive"))
    )
    (net (code "65") (name "PBGND") (class "Default")
      (node (ref "ABS") (pin "2") (pinfunction "2_2") (pintype "passive"))
      (node (ref "CON4") (pin "22") (pinfunction "EINT17GPG9_22") (pintype "passive"))
      (node (ref "CON4") (pin "24") (pinfunction "K6/EINT19/GPG11_24") (pintype "passive"))
      (node (ref "GPG0") (pin "2") (pinfunction "2_2") (pintype "passive"))
      (node (ref "PRES") (pin "2") (pinfunction "2_2") (pintype "passive"))
      (node (ref "SGG") (pin "2") (pinfunction "2_2") (pintype "passive"))
    )
    (net (code "66") (name "PRES") (class "Default")
      (node (ref "CON4") (pin "8") (pinfunction "AN3_8") (pintype "passive"))
      (node (ref "PRES") (pin "1") (pinfunction "1_1") (pintype "passive"))
    )
    (net (code "67") (name "SGG") (class "Default")
      (node (ref "CON4") (pin "21") (pinfunction "K5/EINT15/GPG7_21") (pintype "passive"))
      (node (ref "SGG") (pin "1") (pinfunction "1_1") (pintype "passive"))
    )
    (net (code "68") (name "SPICLK") (class "Default")
      (node (ref "A1") (pin "1") (pinfunction "SCLK_1") (pintype "power_in"))
      (node (ref "CON4") (pin "27") (pinfunction "SPICLK_27") (pintype "passive"))
    )
    (net (code "69") (name "SPIMISO") (class "Default")
      (node (ref "A1") (pin "9") (pinfunction "DOUT_9") (pintype "input"))
      (node (ref "CON4") (pin "25") (pinfunction "SPIMISO_25") (pintype "passive"))
    )
    (net (code "70") (name "SPIMOSI") (class "Default")
      (node (ref "A1") (pin "10") (pinfunction "DIN_10") (pintype "input"))
      (node (ref "CON4") (pin "26") (pinfunction "SPIMOSI_26") (pintype "passive"))
    )
    (net (code "71") (name "SW") (class "Default")
      (node (ref "CON4") (pin "18") (pinfunction "K2/EINT11/GPG3_18") (pintype "passive"))
      (node (ref "R20") (pin "1") (pinfunction "1_1") (pintype "passive"))
      (node (ref "U5") (pin "1") (pinfunction "OUT_1") (pintype "open_collector"))
    )
    (net (code "72") (name "TSXM") (class "Default")
      (node (ref "JMINI") (pin "37") (pinfunction "37_37") (pintype "passive"))
      (node (ref "TS") (pin "1") (pinfunction "1_1") (pintype "passive"))
      (node (ref "V2") (pin "1") (pinfunction "1_1") (pintype "passive"))
    )
    (net (code "73") (name "TSXP") (class "Default")
      (node (ref "JMINI") (pin "38") (pinfunction "38_38") (pintype "passive"))
      (node (ref "TS") (pin "3") (pinfunction "3_3") (pintype "passive"))
      (node (ref "V4") (pin "1") (pinfunction "1_1") (pintype "passive"))
    )
    (net (code "74") (name "TSYM") (class "Default")
      (node (ref "JMINI") (pin "39") (pinfunction "39_39") (pintype "passive"))
      (node (ref "TS") (pin "2") (pinfunction "2_2") (pintype "passive"))
      (node (ref "V1") (pin "1") (pinfunction "1_1") (pintype "passive"))
    )
    (net (code "75") (name "TSYP") (class "Default")
      (node (ref "JMINI") (pin "40") (pinfunction "40_40") (pintype "passive"))
      (node (ref "TS") (pin "4") (pinfunction "4_4") (pintype "passive"))
      (node (ref "V3") (pin "1") (pinfunction "1_1") (pintype "passive"))
    )
    (net (code "76") (name "VCC") (class "Default")
      (node (ref "A1") (pin "8") (pinfunction "VDD_8") (pintype "input"))
      (node (ref "C1") (pin "2") (pinfunction "2_2") (pintype "passive"))
      (node (ref "C10") (pin "2") (pinfunction "2_2") (pintype "passive"))
      (node (ref "C17") (pin "2") (pinfunction "2_2") (pintype "passive"))
      (node (ref "C2") (pin "2") (pinfunction "2_2") (pintype "passive"))
      (node (ref "C4") (pin "2") (pinfunction "2_2") (pintype "passive"))
      (node (ref "C5") (pin "2") (pinfunction "2_2") (pintype "passive"))
      (node (ref "C9") (pin "2") (pinfunction "2_2") (pintype "passive"))
      (node (ref "R11") (pin "1") (pinfunction "1_1") (pintype "passive"))
      (node (ref "R12") (pin "1") (pinfunction "1_1") (pintype "passive"))
      (node (ref "R9") (pin "2") (pinfunction "2_2") (pintype "passive"))
      (node (ref "U1") (pin "2") (pinfunction "VS_2") (pintype "power_in"))
      (node (ref "U1") (pin "6") (pintype "input"))
      (node (ref "U2") (pin "2") (pinfunction "VS_2") (pintype "power_in"))
      (node (ref "U2") (pin "6") (pintype "input"))
      (node (ref "U3") (pin "2") (pinfunction "VS_2") (pintype "power_in"))
      (node (ref "U3") (pin "6") (pintype "input"))
      (node (ref "U4") (pin "2") (pinfunction "OUT_2") (pintype "power_in"))
    )
    (net (code "77") (name "VDD") (class "Default")
      (node (ref "CON4") (pin "1") (pinfunction "VDD5V_1") (pintype "passive"))
      (node (ref "JMINI") (pin "1") (pinfunction "1_1") (pintype "passive"))
      (node (ref "JMINI") (pin "2") (pinfunction "2_2") (pintype "passive"))
      (node (ref "JTCON") (pin "3") (pinfunction "3_3") (pintype "passive"))
      (node (ref "JTCON") (pin "4") (pinfunction "4_4") (pintype "passive"))
      (node (ref "JTCON") (pin "5") (pinfunction "5_5") (pintype "passive"))
      (node (ref "JTCON") (pin "6") (pinfunction "6_6") (pintype "passive"))
      (node (ref "JTCON") (pin "7") (pinfunction "7_7") (pintype "passive"))
      (node (ref "K1") (pin "5") (pinfunction "5_5") (pintype "passive"))
      (node (ref "R18") (pin "1") (pinfunction "1_1") (pintype "passive"))
      (node (ref "R2") (pin "2") (pinfunction "2_2") (pintype "passive"))
      (node (ref "VDD") (pin "1") (pinfunction "1_1") (pintype "passive"))
    )
    (net (code "78") (name "VEE") (class "Default")
      (node (ref "K1") (pin "4") (pinfunction "4_4") (pintype "passive"))
      (node (ref "LA") (pin "2") (pinfunction "2_2") (pintype "passive"))
      (node (ref "LB") (pin "2") (pinfunction "2_2") (pintype "passive"))
      (node (ref "LR") (pin "2") (pinfunction "2_2") (pintype "passive"))
      (node (ref "U4") (pin "1") (pinfunction "IN_1") (pintype "power_in"))
      (node (ref "U5") (pin "8") (pinfunction "V+_8") (pintype "power_in"))
    )
    (net (code "79") (name "nSS_SPI") (class "Default")
      (node (ref "CON4") (pin "28") (pinfunction "nSS_SPI_28") (pintype "passive"))
      (node (ref "R17") (pin "1") (pinfunction "1_1") (pintype "passive"))
      (node (ref "R18") (pin "2") (pinfunction "2_2") (pintype "passive"))
      (node (ref "R19") (pin "1") (pinfunction "1_1") (pintype "passive"))
      (node (ref "U5") (pin "5") (pinfunction "IN+_5") (pintype "input"))
    )
    (net (code "80") (name "unconnected-(CON4-AN0-Pad5)") (class "Default")
      (node (ref "CON4") (pin "5") (pinfunction "AN0_5") (pintype "passive"))
    )
    (net (code "81") (name "unconnected-(CON4-AN2-Pad7)") (class "Default")
      (node (ref "CON4") (pin "7") (pinfunction "AN2_7") (pintype "passive"))
    )
    (net (code "82") (name "unconnected-(CON4-CLKOUT0-Pad33)") (class "Default")
      (node (ref "CON4") (pin "33") (pinfunction "CLKOUT0_33") (pintype "passive"))
    )
    (net (code "83") (name "unconnected-(CON4-CLKOUT1-Pad34)") (class "Default")
      (node (ref "CON4") (pin "34") (pinfunction "CLKOUT1_34") (pintype "passive"))
    )
    (net (code "84") (name "unconnected-(CON4-EINT1{slash}GPF1-Pad10)") (class "Default")
      (node (ref "CON4") (pin "10") (pinfunction "EINT1/GPF1_10") (pintype "passive"))
    )
    (net (code "85") (name "unconnected-(CON4-EINT2{slash}GPF2-Pad11)") (class "Default")
      (node (ref "CON4") (pin "11") (pinfunction "EINT2/GPF2_11") (pintype "passive"))
    )
    (net (code "86") (name "unconnected-(CON4-EINT6{slash}GPF6-Pad15)") (class "Default")
      (node (ref "CON4") (pin "15") (pinfunction "EINT6/GPF6_15") (pintype "passive"))
    )
    (net (code "87") (name "unconnected-(CON4-EINT9{slash}GPG1-Pad17)") (class "Default")
      (node (ref "CON4") (pin "17") (pinfunction "EINT9/GPG1_17") (pintype "passive"))
    )
    (net (code "88") (name "unconnected-(CON4-EINT18{slash}GPG10-Pad23)") (class "Default")
      (node (ref "CON4") (pin "23") (pinfunction "EINT18/GPG10_23") (pintype "passive"))
    )
    (net (code "89") (name "unconnected-(CON4-GPB0{slash}BUZZ-Pad31)") (class "Default")
      (node (ref "CON4") (pin "31") (pinfunction "GPB0/BUZZ_31") (pintype "passive"))
    )
    (net (code "90") (name "unconnected-(CON4-I2CSCL-Pad29)") (class "Default")
      (node (ref "CON4") (pin "29") (pinfunction "I2CSCL_29") (pintype "passive"))
    )
    (net (code "91") (name "unconnected-(CON4-I2CSDA-Pad30)") (class "Default")
      (node (ref "CON4") (pin "30") (pinfunction "I2CSDA_30") (pintype "passive"))
    )
    (net (code "92") (name "unconnected-(CON4-K3{slash}EINT13{slash}GPG5-Pad19)") (class "Default")
      (node (ref "CON4") (pin "19") (pinfunction "K3/EINT13/GPG5_19") (pintype "passive"))
    )
    (net (code "93") (name "unconnected-(CON4-VDD3V-Pad2)") (class "Default")
      (node (ref "CON4") (pin "2") (pinfunction "VDD3V_2") (pintype "passive"))
    )
    (net (code "94") (name "unconnected-(CON4-nRESET-Pad4)") (class "Default")
      (node (ref "CON4") (pin "4") (pinfunction "nRESET_4") (pintype "passive"))
    )
    (net (code "95") (name "unconnected-(K1-Pad3)") (class "Default")
      (node (ref "K1") (pin "3") (pinfunction "3_3") (pintype "passive"))
    )
    (net (code "96") (name "unconnected-(K1-Pad6)") (class "Default")
      (node (ref "K1") (pin "6") (pinfunction "6_6") (pintype "passive"))
    )
    (net (code "97") (name "unconnected-(PWR-Pad4)") (class "Default")
      (node (ref "PWR") (pin "4") (pinfunction "4_4") (pintype "passive"))
    )
    (net (code "98") (name "unconnected-(U1-Pad1)") (class "Default")
      (node (ref "U1") (pin "1") (pintype "power_in"))
    )
    (net (code "99") (name "unconnected-(U1-Pad5)") (class "Default")
      (node (ref "U1") (pin "5") (pintype "input"))
    )
    (net (code "100") (name "unconnected-(U1-Pad7)") (class "Default")
      (node (ref "U1") (pin "7") (pintype "input"))
    )
    (net (code "101") (name "unconnected-(U1-Pad8)") (class "Default")
      (node (ref "U1") (pin "8") (pintype "output"))
    )
    (net (code "102") (name "unconnected-(U2-Pad1)") (class "Default")
      (node (ref "U2") (pin "1") (pintype "power_in"))
    )
    (net (code "103") (name "unconnected-(U2-Pad5)") (class "Default")
      (node (ref "U2") (pin "5") (pintype "input"))
    )
    (net (code "104") (name "unconnected-(U2-Pad7)") (class "Default")
      (node (ref "U2") (pin "7") (pintype "input"))
    )
    (net (code "105") (name "unconnected-(U2-Pad8)") (class "Default")
      (node (ref "U2") (pin "8") (pintype "output"))
    )
    (net (code "106") (name "unconnected-(U3-Pad1)") (class "Default")
      (node (ref "U3") (pin "1") (pintype "power_in"))
    )
    (net (code "107") (name "unconnected-(U3-Pad5)") (class "Default")
      (node (ref "U3") (pin "5") (pintype "input"))
    )
    (net (code "108") (name "unconnected-(U3-Pad7)") (class "Default")
      (node (ref "U3") (pin "7") (pintype "input"))
    )
    (net (code "109") (name "unconnected-(U3-Pad8)") (class "Default")
      (node (ref "U3") (pin "8") (pintype "output"))
    )
    (net (code "110") (name "unconnected-(U10-I{slash}O_1-Pad1)") (class "Default")
      (node (ref "U10") (pin "1") (pinfunction "I/O_1_1") (pintype "power_in"))
    )
    (net (code "111") (name "unconnected-(U10-I{slash}O_2-Pad3)") (class "Default")
      (node (ref "U10") (pin "3") (pinfunction "I/O_2_3") (pintype "power_in"))
    )
    (net (code "112") (name "unconnected-(U10-VDD-Pad5)") (class "Default")
      (node (ref "U10") (pin "5") (pinfunction "VDD_5") (pintype "input"))
    )
  )
)
